# 612_jetracer_esp32s3_030003.net
KiCad netlist of a schematic drawn in EAGLE
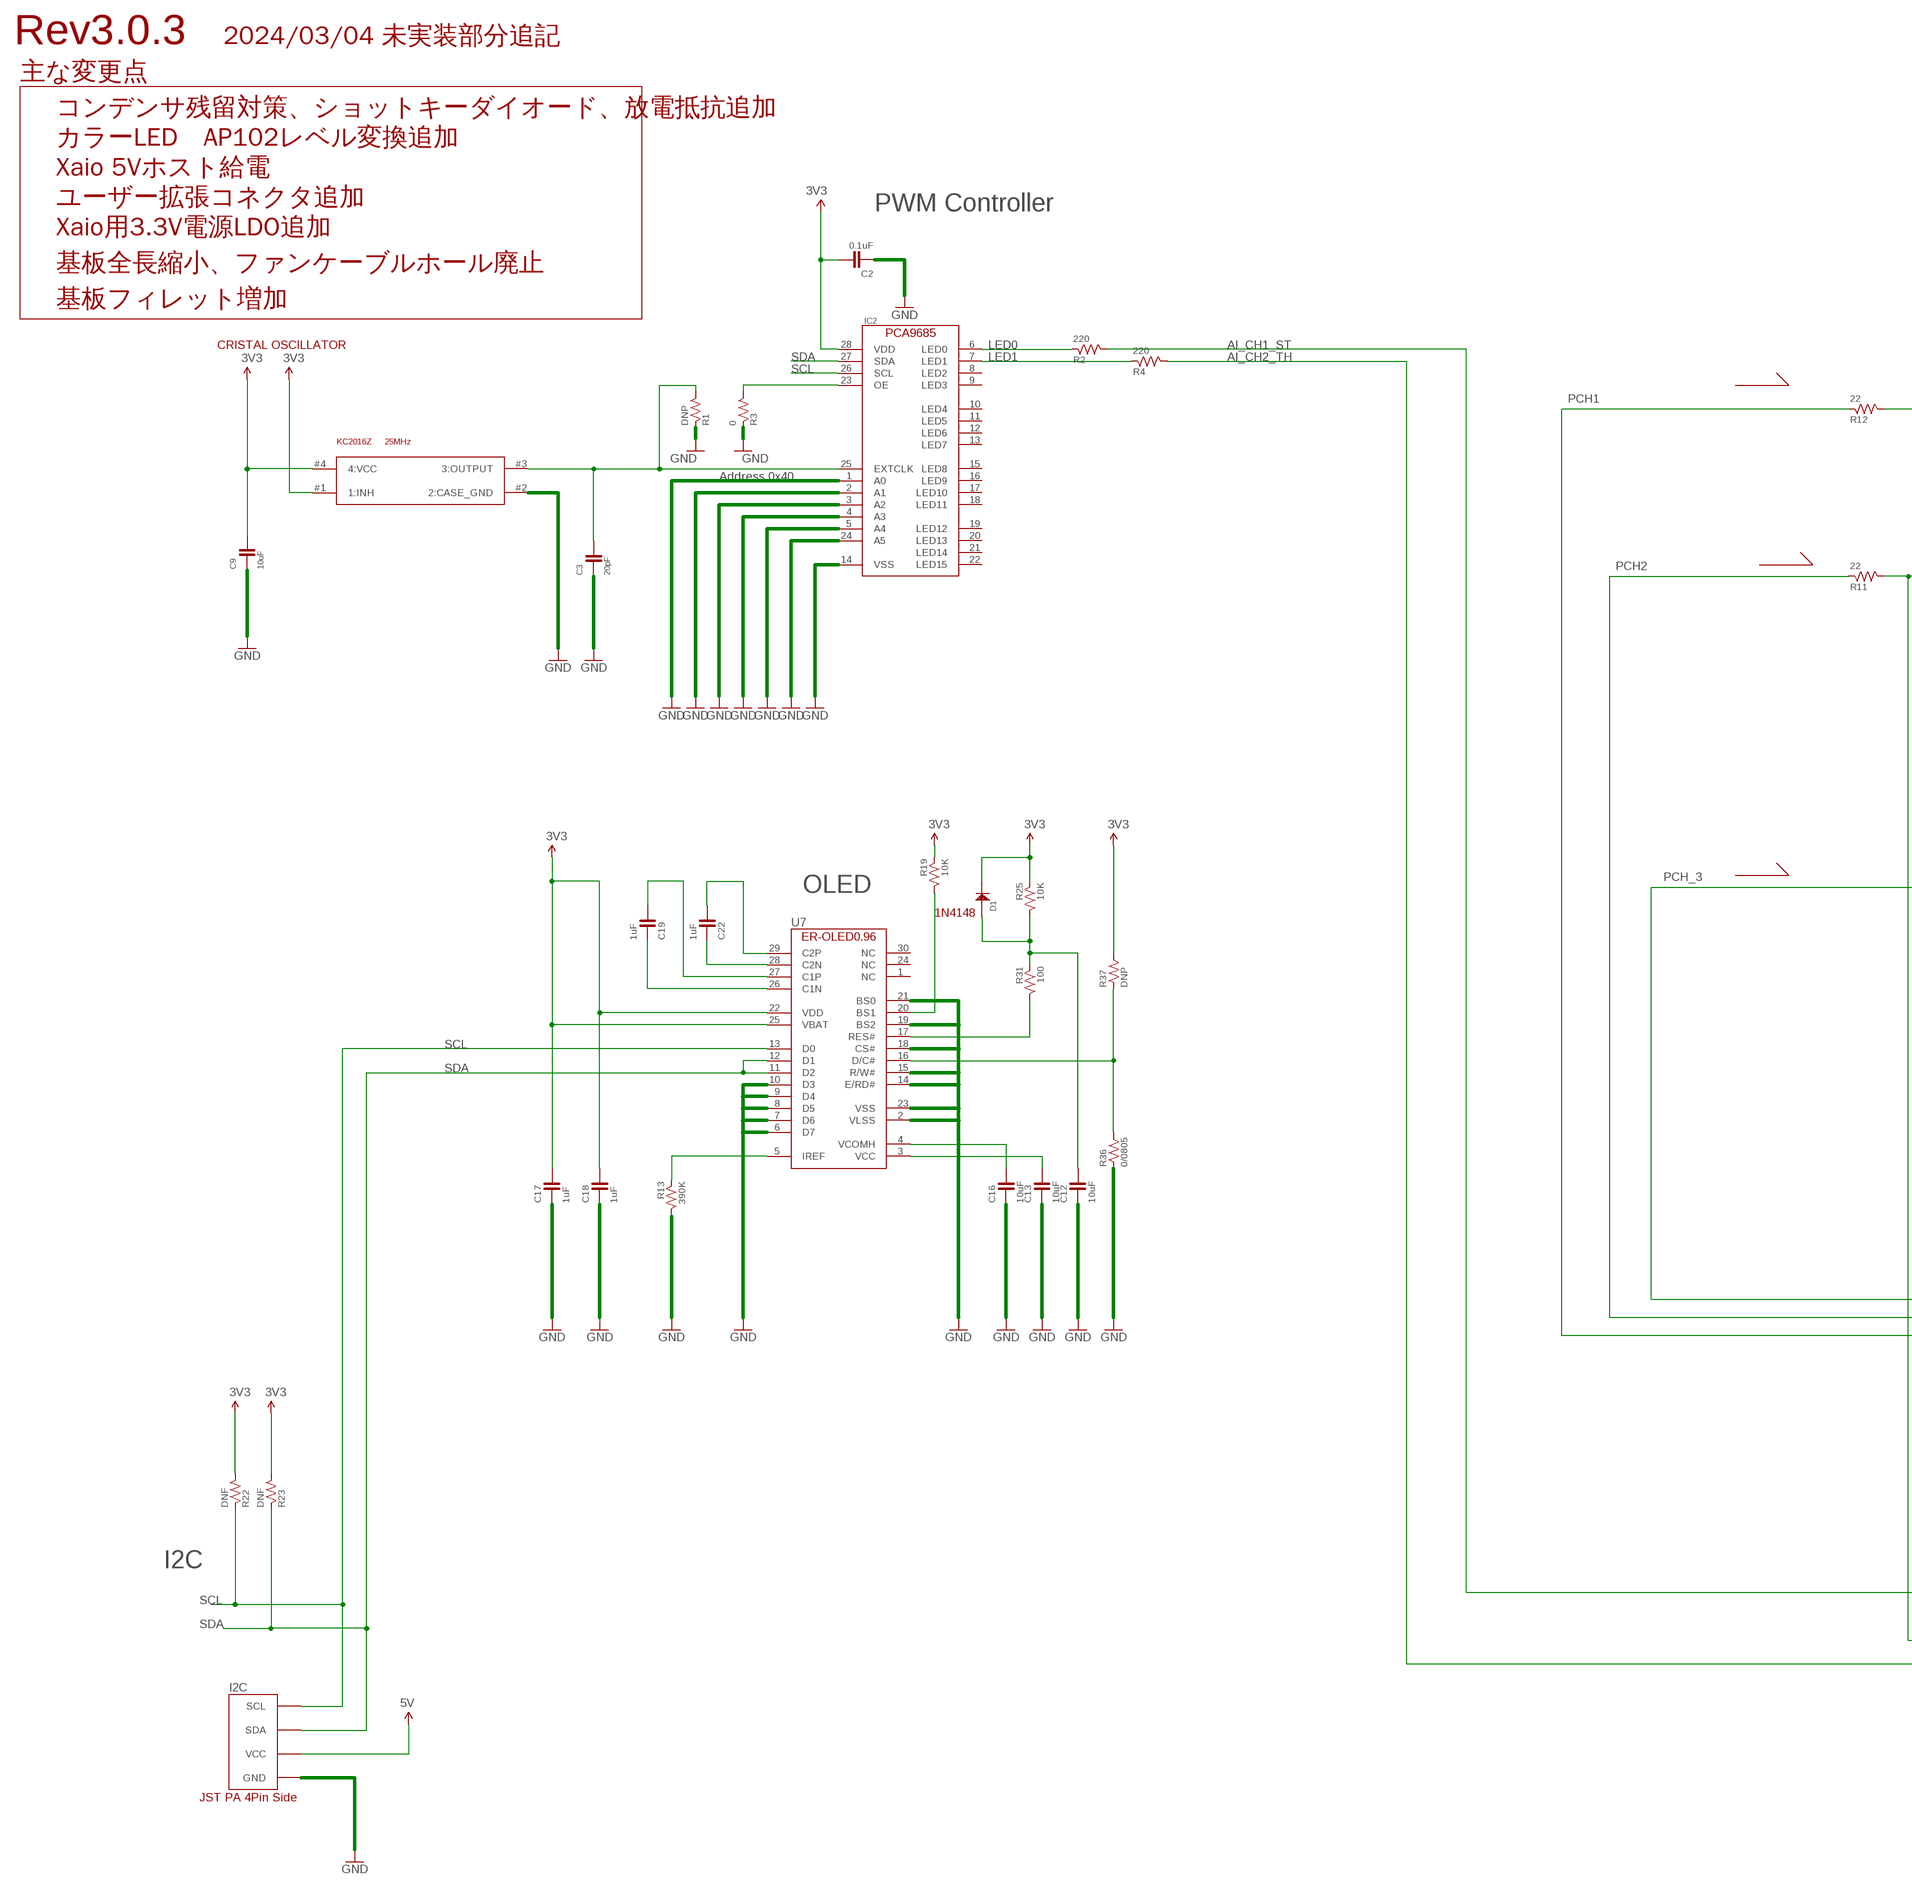
[diagram p0: schematic, sheet 1, part 1 of 3]
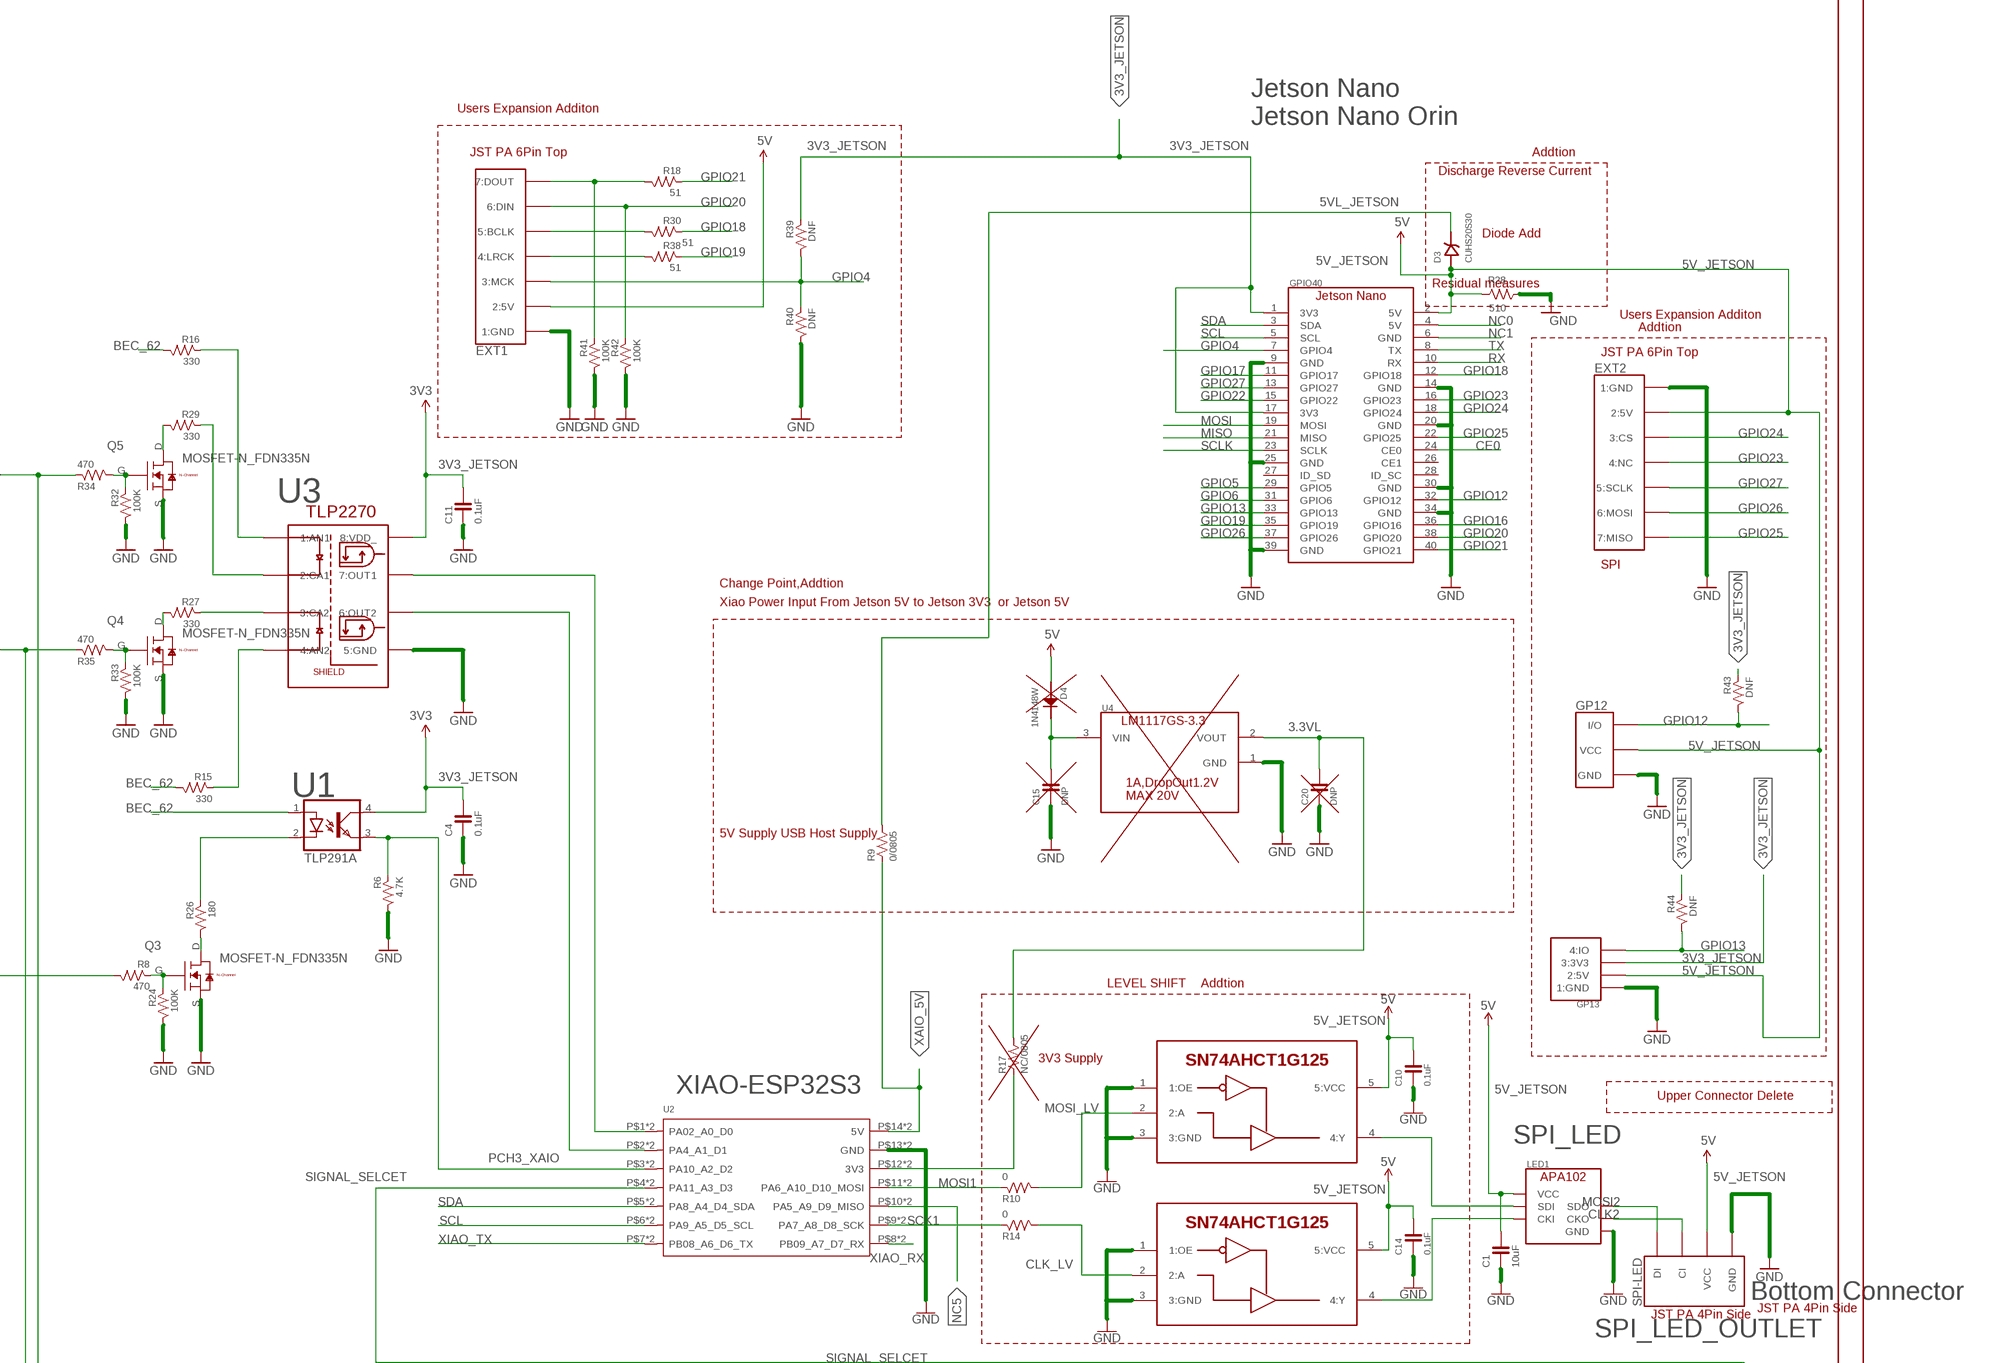
[diagram p1: schematic, sheet 1, part 2 of 3]
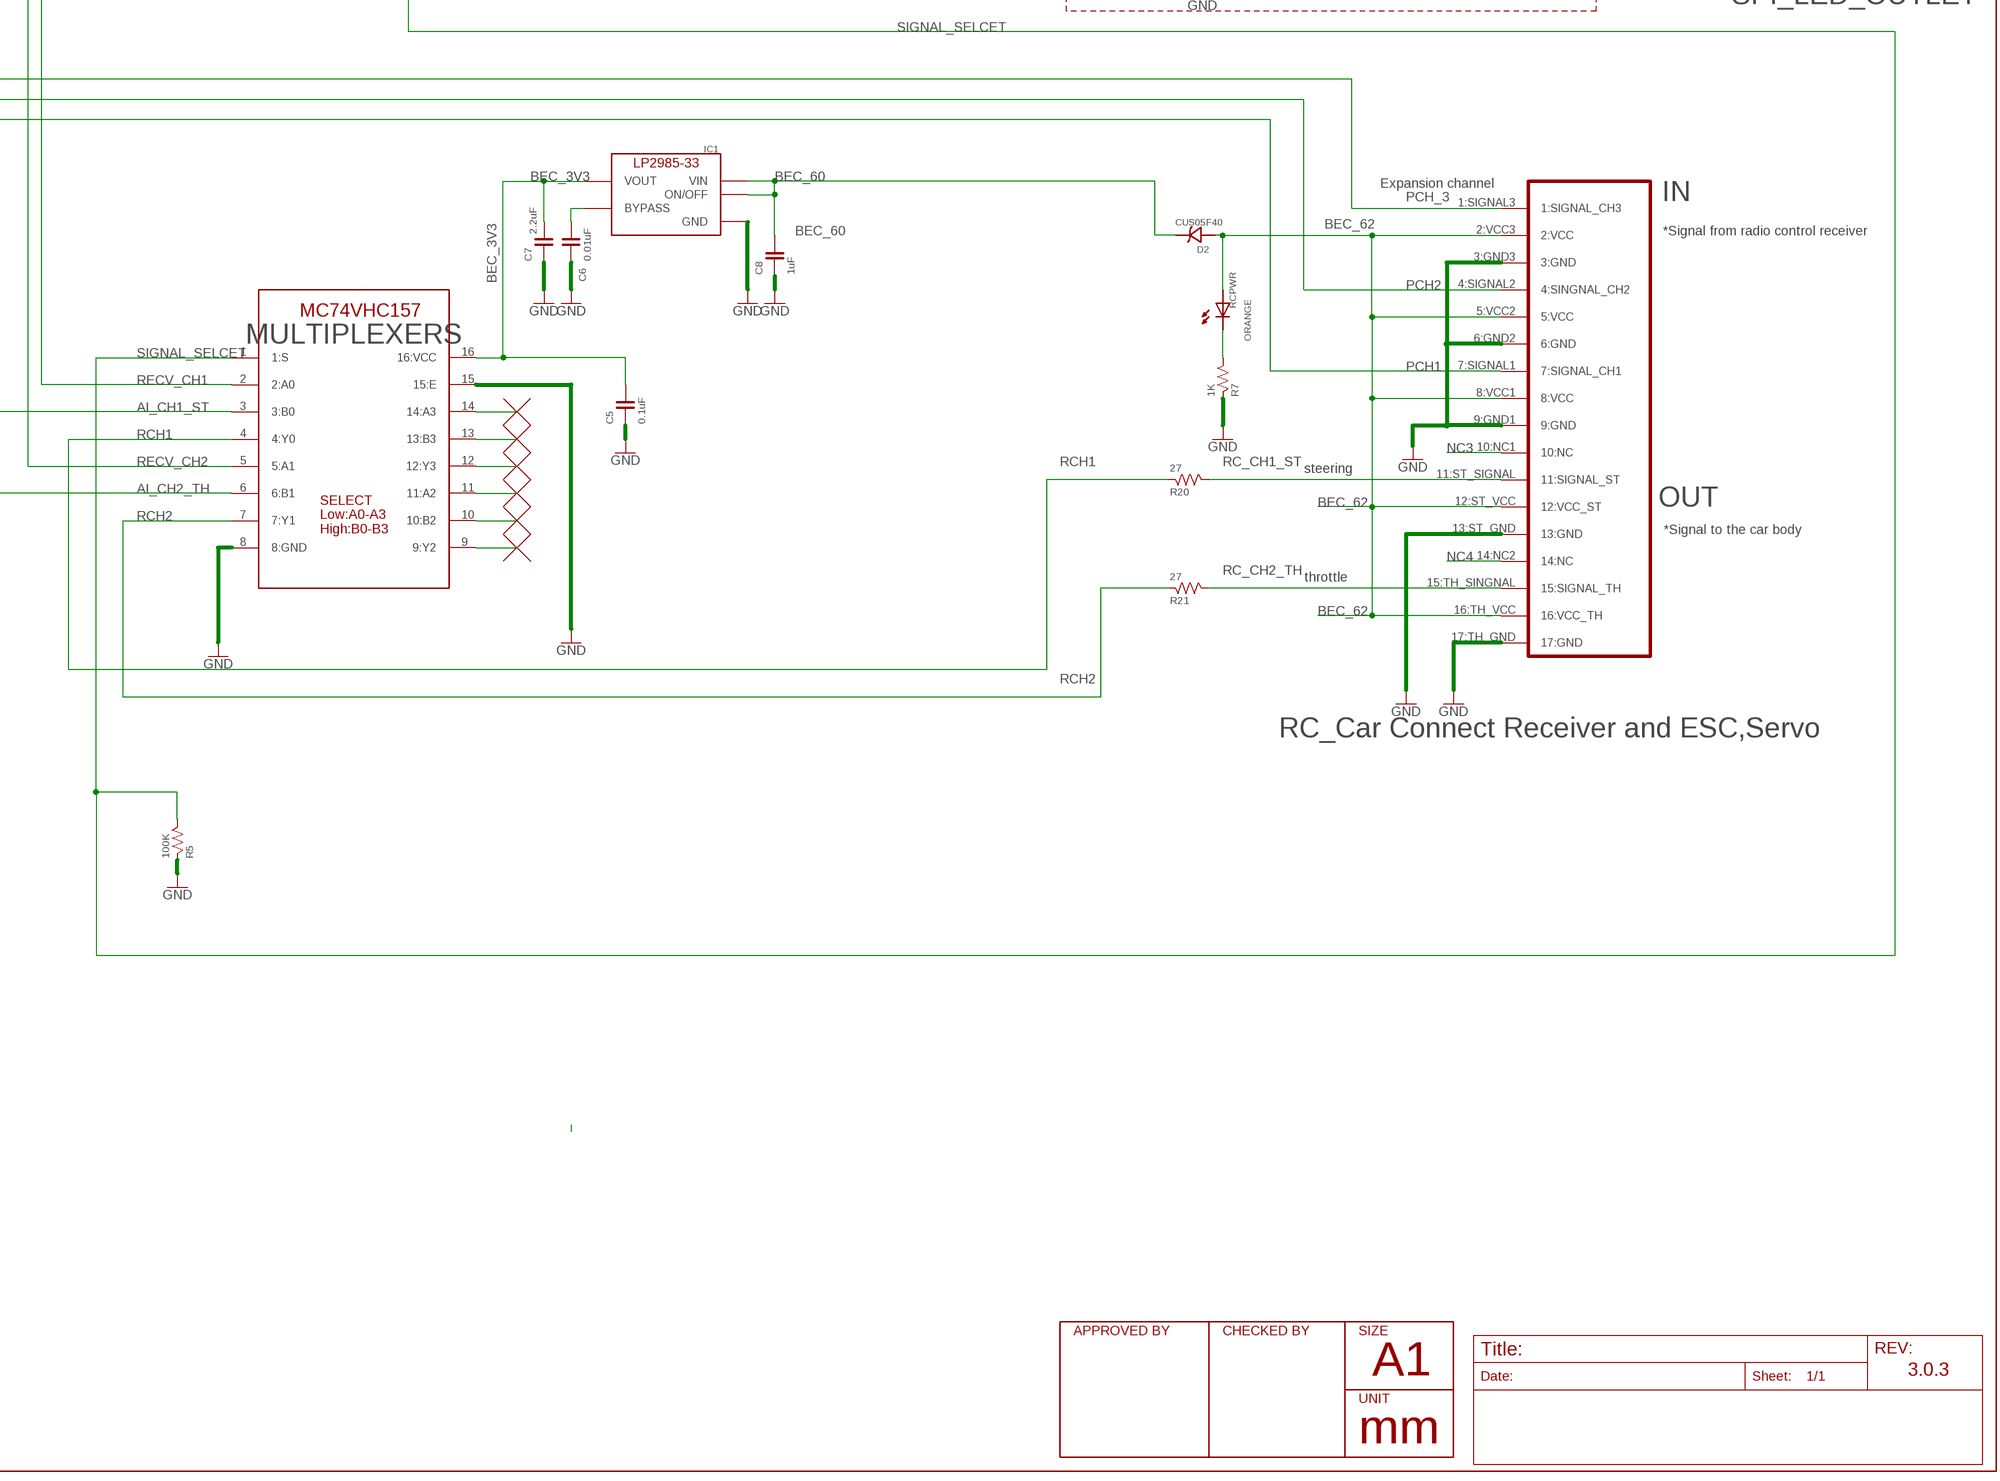
[diagram p2: schematic, sheet 1, part 3 of 3]

(export (version "E")
  (design (tool "Eeschema 10.0.6"))
  (components
    (comp (ref "C1")
      (value "10uF")
      (footprint "eagle-import:0603")
      (libsource (lib "eagle-import") (part "CAPACITOR-0603"))
    )
    (comp (ref "C2")
      (value "0.1uF")
      (footprint "eagle-import:0603")
      (libsource (lib "eagle-import") (part "CAPACITOR-0603"))
    )
    (comp (ref "C3")
      (value "20pF")
      (footprint "eagle-import:0402")
      (libsource (lib "eagle-import") (part "CAPACITOR-0402"))
    )
    (comp (ref "C4")
      (value "0.1uF")
      (footprint "eagle-import:0603")
      (libsource (lib "eagle-import") (part "CAPACITOR-0603"))
    )
    (comp (ref "C5")
      (value "0.1uF")
      (footprint "eagle-import:0603")
      (libsource (lib "eagle-import") (part "CAPACITOR-0603"))
    )
    (comp (ref "C6")
      (value "0.01uF")
      (footprint "eagle-import:0603")
      (libsource (lib "eagle-import") (part "CAPACITOR-0603"))
    )
    (comp (ref "C7")
      (value "2.2uF")
      (footprint "eagle-import:0603")
      (libsource (lib "eagle-import") (part "CAPACITOR-0603"))
    )
    (comp (ref "C8")
      (value "1uF")
      (footprint "eagle-import:0603")
      (libsource (lib "eagle-import") (part "CAPACITOR-0603"))
    )
    (comp (ref "C9")
      (value "10uF")
      (footprint "eagle-import:0402")
      (libsource (lib "eagle-import") (part "CAPACITOR-0402"))
    )
    (comp (ref "C10")
      (value "0.1uF")
      (footprint "eagle-import:0402")
      (libsource (lib "eagle-import") (part "CAPACITOR-0402"))
    )
    (comp (ref "C11")
      (value "0.1uF")
      (footprint "eagle-import:0603")
      (libsource (lib "eagle-import") (part "CAPACITOR-0603"))
    )
    (comp (ref "C12")
      (value "10uF")
      (footprint "eagle-import:0603")
      (libsource (lib "eagle-import") (part "CAPACITOR-0603"))
    )
    (comp (ref "C13")
      (value "10uF")
      (footprint "eagle-import:0603")
      (libsource (lib "eagle-import") (part "CAPACITOR-0603"))
    )
    (comp (ref "C14")
      (value "0.1uF")
      (footprint "eagle-import:0402")
      (libsource (lib "eagle-import") (part "CAPACITOR-0402"))
    )
    (comp (ref "C15")
      (value "DNP")
      (footprint "eagle-import:0402")
      (libsource (lib "eagle-import") (part "CAPACITOR-0402"))
    )
    (comp (ref "C16")
      (value "10uF")
      (footprint "eagle-import:0603")
      (libsource (lib "eagle-import") (part "CAPACITOR-0603"))
    )
    (comp (ref "C17")
      (value "1uF")
      (footprint "eagle-import:0603")
      (libsource (lib "eagle-import") (part "CAPACITOR-0603"))
    )
    (comp (ref "C18")
      (value "1uF")
      (footprint "eagle-import:0603")
      (libsource (lib "eagle-import") (part "CAPACITOR-0603"))
    )
    (comp (ref "C19")
      (value "1uF")
      (footprint "eagle-import:0603")
      (libsource (lib "eagle-import") (part "CAPACITOR-0603"))
    )
    (comp (ref "C20")
      (value "DNP")
      (footprint "eagle-import:0402")
      (libsource (lib "eagle-import") (part "CAPACITOR-0402"))
    )
    (comp (ref "C22")
      (value "1uF")
      (footprint "eagle-import:0603")
      (libsource (lib "eagle-import") (part "CAPACITOR-0603"))
    )
    (comp (ref "D1")
      (value "1N4148")
      (footprint "eagle-import:1N4148W")
      (libsource (lib "eagle-import") (part "1N4148"))
    )
    (comp (ref "D2")
      (value "CUS05F40")
      (footprint "eagle-import:CUS05F40")
      (libsource (lib "eagle-import") (part "CUS05F40"))
    )
    (comp (ref "D3")
      (value "CUHS20S30")
      (footprint "eagle-import:US2H")
      (libsource (lib "eagle-import") (part "CUHS20S30"))
    )
    (comp (ref "D4")
      (value "1N4148W")
      (footprint "eagle-import:SOD-123")
      (libsource (lib "eagle-import") (part "1N4148W"))
    )
    (comp (ref "EXT1")
      (value "FABO-I2S-7PIN")
      (footprint "eagle-import:SPI-B07B-PASK-1")
      (libsource (lib "eagle-import") (part "FABO-I2S-7PIN"))
    )
    (comp (ref "EXT2")
      (value "FABO-SPI-7PIN")
      (footprint "eagle-import:SPI-B07B-PASK-1")
      (libsource (lib "eagle-import") (part "FABO-SPI-7PIN"))
    )
    (comp (ref "GP12")
      (value "FABO_BRICK_3PIN-B03B-PASK-1")
      (footprint "eagle-import:FABO_BRICK_3PIN_B03B-PASK-1")
      (libsource (lib "eagle-import") (part "FABO_BRICK_3PIN-B03B-PASK-1"))
    )
    (comp (ref "GP13")
      (value "FABO-GPIO-2G")
      (footprint "eagle-import:GPIO-B04B-PASK-1")
      (libsource (lib "eagle-import") (part "FABO-GPIO-2G"))
    )
    (comp (ref "GPIO40")
      (value "JETSON_NANOJETSON_NANO_OVERALL")
      (footprint "eagle-import:JETSON_NANO_DEMENTION")
      (libsource (lib "eagle-import") (part "JETSON_NANOJETSON_NANO_OVERALL"))
    )
    (comp (ref "I2C")
      (value "FABO-I2C")
      (footprint "eagle-import:I2C-SM04B-PASS-1-FL")
      (libsource (lib "eagle-import") (part "FABO-I2C"))
    )
    (comp (ref "IC1")
      (value "LP2985-33DBVR")
      (footprint "eagle-import:SOT-23-5")
      (libsource (lib "eagle-import") (part "LP2985-33DBVR"))
    )
    (comp (ref "IC2")
      (value "PCA9685PW,BS")
      (footprint "eagle-import:PCA9685")
      (libsource (lib "eagle-import") (part "PCA9685PW,BS"))
    )
    (comp (ref "LED1")
      (value "APA102_IPIXEL")
      (footprint "eagle-import:APA102_2020")
      (libsource (lib "eagle-import") (part "APA102_IPIXEL"))
    )
    (comp (ref "Q3")
      (value "MOSFET-N_FDN335N")
      (footprint "eagle-import:SUPERSOT-3")
      (libsource (lib "eagle-import") (part "MOSFET-N_FDN335N"))
    )
    (comp (ref "Q4")
      (value "MOSFET-N_FDN335N")
      (footprint "eagle-import:SUPERSOT-3")
      (libsource (lib "eagle-import") (part "MOSFET-N_FDN335N"))
    )
    (comp (ref "Q5")
      (value "MOSFET-N_FDN335N")
      (footprint "eagle-import:SUPERSOT-3")
      (libsource (lib "eagle-import") (part "MOSFET-N_FDN335N"))
    )
    (comp (ref "R1")
      (value "DNP")
      (footprint "eagle-import:0603")
      (libsource (lib "eagle-import") (part "RESISTOR-0603"))
    )
    (comp (ref "R2")
      (value "220")
      (footprint "eagle-import:0603")
      (libsource (lib "eagle-import") (part "RESISTOR-0603"))
    )
    (comp (ref "R3")
      (value "0")
      (footprint "eagle-import:0603")
      (libsource (lib "eagle-import") (part "RESISTOR-0603"))
    )
    (comp (ref "R4")
      (value "220")
      (footprint "eagle-import:0603")
      (libsource (lib "eagle-import") (part "RESISTOR-0603"))
    )
    (comp (ref "R5")
      (value "100K")
      (footprint "eagle-import:0603")
      (libsource (lib "eagle-import") (part "RESISTOR-0603"))
    )
    (comp (ref "R6")
      (value "4.7K")
      (footprint "eagle-import:0603")
      (libsource (lib "eagle-import") (part "RESISTOR-0603"))
    )
    (comp (ref "R7")
      (value "1K")
      (footprint "eagle-import:0603")
      (libsource (lib "eagle-import") (part "RESISTOR-0603"))
    )
    (comp (ref "R8")
      (value "470")
      (footprint "eagle-import:0603")
      (libsource (lib "eagle-import") (part "RESISTOR-0603"))
    )
    (comp (ref "R9")
      (value "0/0805")
      (footprint "eagle-import:0805")
      (libsource (lib "eagle-import") (part "RESISTOR-0805"))
    )
    (comp (ref "R10")
      (value "0")
      (footprint "eagle-import:0603")
      (libsource (lib "eagle-import") (part "RESISTOR-0603"))
    )
    (comp (ref "R11")
      (value "22")
      (footprint "eagle-import:0603")
      (libsource (lib "eagle-import") (part "RESISTOR-0603"))
    )
    (comp (ref "R12")
      (value "22")
      (footprint "eagle-import:0603")
      (libsource (lib "eagle-import") (part "RESISTOR-0603"))
    )
    (comp (ref "R13")
      (value "390K")
      (footprint "eagle-import:0603")
      (libsource (lib "eagle-import") (part "RESISTOR-0603"))
    )
    (comp (ref "R14")
      (value "0")
      (footprint "eagle-import:0603")
      (libsource (lib "eagle-import") (part "RESISTOR-0603"))
    )
    (comp (ref "R15")
      (value "330")
      (footprint "eagle-import:0603")
      (libsource (lib "eagle-import") (part "RESISTOR-0603"))
    )
    (comp (ref "R16")
      (value "330")
      (footprint "eagle-import:0603")
      (libsource (lib "eagle-import") (part "RESISTOR-0603"))
    )
    (comp (ref "R17")
      (value "NC/0805")
      (footprint "eagle-import:0805")
      (libsource (lib "eagle-import") (part "RESISTOR-0805"))
    )
    (comp (ref "R18")
      (value "51")
      (footprint "eagle-import:0603")
      (libsource (lib "eagle-import") (part "RESISTOR-0603"))
    )
    (comp (ref "R19")
      (value "10K")
      (footprint "eagle-import:0603")
      (libsource (lib "eagle-import") (part "RESISTOR-0603"))
    )
    (comp (ref "R20")
      (value "27")
      (footprint "eagle-import:0603")
      (libsource (lib "eagle-import") (part "RESISTOR-0603"))
    )
    (comp (ref "R21")
      (value "27")
      (footprint "eagle-import:0603")
      (libsource (lib "eagle-import") (part "RESISTOR-0603"))
    )
    (comp (ref "R22")
      (value "DNF")
      (footprint "eagle-import:0603")
      (libsource (lib "eagle-import") (part "RESISTOR-0603"))
    )
    (comp (ref "R23")
      (value "DNF")
      (footprint "eagle-import:0603")
      (libsource (lib "eagle-import") (part "RESISTOR-0603"))
    )
    (comp (ref "R24")
      (value "100K")
      (footprint "eagle-import:0603")
      (libsource (lib "eagle-import") (part "RESISTOR-0603"))
    )
    (comp (ref "R25")
      (value "10K")
      (footprint "eagle-import:0603")
      (libsource (lib "eagle-import") (part "RESISTOR-0603"))
    )
    (comp (ref "R26")
      (value "180")
      (footprint "eagle-import:0603")
      (libsource (lib "eagle-import") (part "RESISTOR-0603"))
    )
    (comp (ref "R27")
      (value "330")
      (footprint "eagle-import:0603")
      (libsource (lib "eagle-import") (part "RESISTOR-0603"))
    )
    (comp (ref "R28")
      (value "510")
      (footprint "eagle-import:0805")
      (libsource (lib "eagle-import") (part "RESISTOR-0805"))
    )
    (comp (ref "R29")
      (value "330")
      (footprint "eagle-import:0603")
      (libsource (lib "eagle-import") (part "RESISTOR-0603"))
    )
    (comp (ref "R30")
      (value "51")
      (footprint "eagle-import:0603")
      (libsource (lib "eagle-import") (part "RESISTOR-0603"))
    )
    (comp (ref "R31")
      (value "100")
      (footprint "eagle-import:0603")
      (libsource (lib "eagle-import") (part "RESISTOR-0603"))
    )
    (comp (ref "R32")
      (value "100K")
      (footprint "eagle-import:0603")
      (libsource (lib "eagle-import") (part "RESISTOR-0603"))
    )
    (comp (ref "R33")
      (value "100K")
      (footprint "eagle-import:0603")
      (libsource (lib "eagle-import") (part "RESISTOR-0603"))
    )
    (comp (ref "R34")
      (value "470")
      (footprint "eagle-import:0603")
      (libsource (lib "eagle-import") (part "RESISTOR-0603"))
    )
    (comp (ref "R35")
      (value "470")
      (footprint "eagle-import:0603")
      (libsource (lib "eagle-import") (part "RESISTOR-0603"))
    )
    (comp (ref "R36")
      (value "0/0805")
      (footprint "eagle-import:0805")
      (libsource (lib "eagle-import") (part "RESISTOR-0805"))
    )
    (comp (ref "R37")
      (value "DNP")
      (footprint "eagle-import:0805")
      (fields (field (name "SPICEPREFIX") "R"))
      (libsource (lib "eagle-import") (part "RESISTOR-0805"))
    )
    (comp (ref "R38")
      (value "51")
      (footprint "eagle-import:0603")
      (libsource (lib "eagle-import") (part "RESISTOR-0603"))
    )
    (comp (ref "R39")
      (value "DNF")
      (footprint "eagle-import:0603")
      (libsource (lib "eagle-import") (part "RESISTOR-0603"))
    )
    (comp (ref "R40")
      (value "DNF")
      (footprint "eagle-import:0603")
      (libsource (lib "eagle-import") (part "RESISTOR-0603"))
    )
    (comp (ref "R41")
      (value "100K")
      (footprint "eagle-import:0603")
      (libsource (lib "eagle-import") (part "RESISTOR-0603"))
    )
    (comp (ref "R42")
      (value "100K")
      (footprint "eagle-import:0603")
      (libsource (lib "eagle-import") (part "RESISTOR-0603"))
    )
    (comp (ref "R43")
      (value "DNF")
      (footprint "eagle-import:0603")
      (libsource (lib "eagle-import") (part "RESISTOR-0603"))
    )
    (comp (ref "R44")
      (value "DNF")
      (footprint "eagle-import:0603")
      (libsource (lib "eagle-import") (part "RESISTOR-0603"))
    )
    (comp (ref "RCPWR")
      (value "ORANGE")
      (footprint "eagle-import:0603")
      (libsource (lib "eagle-import") (part "LED-0603"))
    )
    (comp (ref "SPI-LED")
      (value "FABO-SPI-LED")
      (footprint "eagle-import:SPI-SM04B-PASS-1-FL")
      (libsource (lib "eagle-import") (part "FABO-SPI-LED"))
    )
    (comp (ref "U$1")
      (value "RC_17PIN_OUTIN")
      (footprint "eagle-import:PNHEADER_2.54_SMT_17PIN_RC_TT01_02")
      (libsource (lib "eagle-import") (part "RC_17PIN_OUTIN"))
    )
    (comp (ref "U$3")
      (value "MC74VHC157")
      (footprint "eagle-import:MC74VHC157_TSSOP-16")
      (libsource (lib "eagle-import") (part "MC74VHC157"))
    )
    (comp (ref "U$9")
      (value "SN74AHCT1G125")
      (footprint "eagle-import:SOT-1DOT1")
      (libsource (lib "eagle-import") (part "SN74AHCT1G125"))
    )
    (comp (ref "U$10")
      (value "SN74AHCT1G125")
      (footprint "eagle-import:SOT-1DOT1")
      (libsource (lib "eagle-import") (part "SN74AHCT1G125"))
    )
    (comp (ref "U$11")
      (value "KC2016Z")
      (footprint "eagle-import:KC2016Z")
      (libsource (lib "eagle-import") (part "KC2016Z"))
    )
    (comp (ref "U1")
      (value "TLP291A")
      (footprint "eagle-import:11-3C1")
      (libsource (lib "eagle-import") (part "TLP291A"))
    )
    (comp (ref "U2")
      (value "MOUDLE-SEEEDUINO-XIAO-ESP32C3")
      (footprint "eagle-import:MOUDLE14P-DIP")
      (libsource (lib "eagle-import") (part "MOUDLE-SEEEDUINO-XIAO-ESP32C3"))
    )
    (comp (ref "U3")
      (value "TLP2270")
      (footprint "eagle-import:TLP2270")
      (libsource (lib "eagle-import") (part "TLP2270"))
    )
    (comp (ref "U4")
      (value "LM1117GS-3.3")
      (footprint "eagle-import:SOT-223-3")
      (libsource (lib "eagle-import") (part "LM1117GS-3.3"))
    )
    (comp (ref "U7")
      (value "ER-OLED0.96-1ER-CON30HT-1")
      (footprint "eagle-import:ER-CON30HT-1")
      (libsource (lib "eagle-import") (part "ER-OLED0.96-1ER-CON30HT-1"))
    )
  )
  (nets
    (net (code "1") (name "/3.3VL") (class "Default")
      (node (ref "C20") (pin "2") (pinfunction "2_2") (pintype "passive"))
      (node (ref "R17") (pin "2") (pinfunction "2_2") (pintype "bidirectional"))
      (node (ref "U4") (pin "2") (pinfunction "VOUT_2") (pintype "output"))
    )
    (net (code "2") (name "/5VL_JETSON") (class "Default")
      (node (ref "D3") (pin "K") (pinfunction "CATHODE_K") (pintype "passive"))
      (node (ref "R9") (pin "2") (pinfunction "2_2") (pintype "bidirectional"))
    )
    (net (code "3") (name "/AI_CH1_ST") (class "Default")
      (node (ref "R2") (pin "2") (pinfunction "2_2") (pintype "bidirectional"))
      (node (ref "U$3") (pin "3") (pinfunction "3:B0_3") (pintype "bidirectional"))
    )
    (net (code "4") (name "/AI_CH2_TH") (class "Default")
      (node (ref "R4") (pin "2") (pinfunction "2_2") (pintype "bidirectional"))
      (node (ref "U$3") (pin "6") (pinfunction "6:B1_6") (pintype "bidirectional"))
    )
    (net (code "5") (name "/BEC_3V3") (class "Default")
      (node (ref "C5") (pin "2") (pinfunction "2_2") (pintype "passive"))
      (node (ref "C7") (pin "2") (pinfunction "2_2") (pintype "passive"))
      (node (ref "IC1") (pin "5") (pinfunction "VOUT_5") (pintype "output"))
      (node (ref "U$3") (pin "16") (pinfunction "16:VCC_16") (pintype "bidirectional"))
    )
    (net (code "6") (name "/BEC_60") (class "Default")
      (node (ref "C8") (pin "2") (pinfunction "2_2") (pintype "passive"))
      (node (ref "D2") (pin "C") (pinfunction "CATHODE_C") (pintype "bidirectional"))
      (node (ref "IC1") (pin "1") (pinfunction "VIN_1") (pintype "input"))
      (node (ref "IC1") (pin "3") (pinfunction "ON/OFF_3") (pintype "input"))
    )
    (net (code "7") (name "/BEC_62") (class "Default")
      (node (ref "D2") (pin "A") (pinfunction "ANODE_A") (pintype "bidirectional"))
      (node (ref "R15") (pin "2") (pinfunction "2_2") (pintype "bidirectional"))
      (node (ref "R16") (pin "2") (pinfunction "2_2") (pintype "bidirectional"))
      (node (ref "RCPWR") (pin "ANODE") (pinfunction "ANODE_ANODE") (pintype "passive"))
      (node (ref "U$1") (pin "12:ST_VCC") (pinfunction "12:VCC_ST_12:ST_VCC") (pintype "bidirectional"))
      (node (ref "U$1") (pin "16:TH_VCC") (pinfunction "16:VCC_TH_16:TH_VCC") (pintype "bidirectional"))
      (node (ref "U$1") (pin "2:VCC3") (pinfunction "2:VCC_2:VCC3") (pintype "bidirectional"))
      (node (ref "U$1") (pin "5:VCC2") (pinfunction "5:VCC_5:VCC2") (pintype "bidirectional"))
      (node (ref "U$1") (pin "8:VCC1") (pinfunction "8:VCC_8:VCC1") (pintype "bidirectional"))
      (node (ref "U1") (pin "1") (pinfunction "A_1") (pintype "passive"))
    )
    (net (code "8") (name "/CE0") (class "Default")
      (node (ref "GPIO40") (pin "24") (pinfunction "CE0_24") (pintype "bidirectional"))
    )
    (net (code "9") (name "/CLK2") (class "Default")
      (node (ref "LED1") (pin "CKO") (pinfunction "CKO_CKO") (pintype "bidirectional"))
      (node (ref "SPI-LED") (pin "CI") (pinfunction "CI_CI") (pintype "bidirectional"))
    )
    (net (code "10") (name "/CLK_LV") (class "Default")
      (node (ref "R14") (pin "2") (pinfunction "2_2") (pintype "bidirectional"))
      (node (ref "U$10") (pin "2") (pinfunction "2:A_2") (pintype "input"))
    )
    (net (code "11") (name "/GPIO4") (class "Default")
      (node (ref "EXT1") (pin "3") (pinfunction "3:MCK_3") (pintype "bidirectional"))
      (node (ref "GPIO40") (pin "7") (pinfunction "GPIO4_7") (pintype "bidirectional"))
      (node (ref "R39") (pin "2") (pinfunction "2_2") (pintype "bidirectional"))
      (node (ref "R40") (pin "1") (pinfunction "1_1") (pintype "bidirectional"))
    )
    (net (code "12") (name "/GPIO5") (class "Default")
      (node (ref "GPIO40") (pin "29") (pinfunction "GPIO5_29") (pintype "bidirectional"))
    )
    (net (code "13") (name "/GPIO6") (class "Default")
      (node (ref "GPIO40") (pin "31") (pinfunction "GPIO6_31") (pintype "bidirectional"))
    )
    (net (code "14") (name "/GPIO12") (class "Default")
      (node (ref "GP12") (pin "I/O") (pinfunction "I/O_I/O") (pintype "bidirectional"))
      (node (ref "GPIO40") (pin "32") (pinfunction "GPIO12_32") (pintype "bidirectional"))
      (node (ref "R43") (pin "2") (pinfunction "2_2") (pintype "bidirectional"))
    )
    (net (code "15") (name "/GPIO13") (class "Default")
      (node (ref "GP13") (pin "IO") (pinfunction "4:IO_IO") (pintype "bidirectional"))
      (node (ref "GPIO40") (pin "33") (pinfunction "GPIO13_33") (pintype "bidirectional"))
      (node (ref "R44") (pin "2") (pinfunction "2_2") (pintype "bidirectional"))
    )
    (net (code "16") (name "/GPIO16") (class "Default")
      (node (ref "GPIO40") (pin "36") (pinfunction "GPIO16_36") (pintype "bidirectional"))
    )
    (net (code "17") (name "/GPIO17") (class "Default")
      (node (ref "GPIO40") (pin "11") (pinfunction "GPIO17_11") (pintype "bidirectional"))
    )
    (net (code "18") (name "/GPIO18") (class "Default")
      (node (ref "GPIO40") (pin "12") (pinfunction "GPIO18_12") (pintype "bidirectional"))
      (node (ref "R30") (pin "1") (pinfunction "1_1") (pintype "bidirectional"))
    )
    (net (code "19") (name "/GPIO19") (class "Default")
      (node (ref "GPIO40") (pin "35") (pinfunction "GPIO19_35") (pintype "bidirectional"))
      (node (ref "R38") (pin "1") (pinfunction "1_1") (pintype "bidirectional"))
    )
    (net (code "20") (name "/GPIO20") (class "Default")
      (node (ref "EXT1") (pin "6") (pinfunction "6:DIN_6") (pintype "bidirectional"))
      (node (ref "GPIO40") (pin "38") (pinfunction "GPIO20_38") (pintype "bidirectional"))
      (node (ref "R42") (pin "1") (pinfunction "1_1") (pintype "bidirectional"))
    )
    (net (code "21") (name "/GPIO21") (class "Default")
      (node (ref "GPIO40") (pin "40") (pinfunction "GPIO21_40") (pintype "bidirectional"))
      (node (ref "R18") (pin "1") (pinfunction "1_1") (pintype "bidirectional"))
    )
    (net (code "22") (name "/GPIO22") (class "Default")
      (node (ref "GPIO40") (pin "15") (pinfunction "GPIO22_15") (pintype "bidirectional"))
    )
    (net (code "23") (name "/GPIO23") (class "Default")
      (node (ref "EXT2") (pin "4") (pinfunction "4:NC_4") (pintype "bidirectional"))
      (node (ref "GPIO40") (pin "16") (pinfunction "GPIO23_16") (pintype "bidirectional"))
    )
    (net (code "24") (name "/GPIO24") (class "Default")
      (node (ref "EXT2") (pin "3") (pinfunction "3:CS_3") (pintype "bidirectional"))
      (node (ref "GPIO40") (pin "18") (pinfunction "GPIO24_18") (pintype "bidirectional"))
    )
    (net (code "25") (name "/GPIO25") (class "Default")
      (node (ref "EXT2") (pin "7") (pinfunction "7:MISO_7") (pintype "bidirectional"))
      (node (ref "GPIO40") (pin "22") (pinfunction "GPIO25_22") (pintype "bidirectional"))
    )
    (net (code "26") (name "/GPIO26") (class "Default")
      (node (ref "EXT2") (pin "6") (pinfunction "6:MOSI_6") (pintype "bidirectional"))
      (node (ref "GPIO40") (pin "37") (pinfunction "GPIO26_37") (pintype "bidirectional"))
    )
    (net (code "27") (name "/GPIO27") (class "Default")
      (node (ref "EXT2") (pin "5") (pinfunction "5:SCLK_5") (pintype "bidirectional"))
      (node (ref "GPIO40") (pin "13") (pinfunction "GPIO27_13") (pintype "bidirectional"))
    )
    (net (code "28") (name "/LED0") (class "Default")
      (node (ref "IC2") (pin "6") (pinfunction "LED0_6") (pintype "bidirectional"))
      (node (ref "R2") (pin "1") (pinfunction "1_1") (pintype "bidirectional"))
    )
    (net (code "29") (name "/LED1") (class "Default")
      (node (ref "IC2") (pin "7") (pinfunction "LED1_7") (pintype "bidirectional"))
      (node (ref "R4") (pin "1") (pinfunction "1_1") (pintype "bidirectional"))
    )
    (net (code "30") (name "/MISO") (class "Default")
      (node (ref "GPIO40") (pin "21") (pinfunction "MISO_21") (pintype "bidirectional"))
    )
    (net (code "31") (name "/MOSI") (class "Default")
      (node (ref "GPIO40") (pin "19") (pinfunction "MOSI_19") (pintype "bidirectional"))
    )
    (net (code "32") (name "/MOSI1") (class "Default")
      (node (ref "R10") (pin "1") (pinfunction "1_1") (pintype "bidirectional"))
      (node (ref "U2") (pin "P$11") (pinfunction "PA6_A10_D10_MOSI_P$11") (pintype "bidirectional"))
      (node (ref "U2") (pin "P$25") (pinfunction "PA6_A10_D10_MOSI_P$25") (pintype "bidirectional"))
    )
    (net (code "33") (name "/MOSI2") (class "Default")
      (node (ref "LED1") (pin "SDO") (pinfunction "SDO_SDO") (pintype "bidirectional"))
      (node (ref "SPI-LED") (pin "DI") (pinfunction "DI_DI") (pintype "bidirectional"))
    )
    (net (code "34") (name "/MOSI_LV") (class "Default")
      (node (ref "R10") (pin "2") (pinfunction "2_2") (pintype "bidirectional"))
      (node (ref "U$9") (pin "2") (pinfunction "2:A_2") (pintype "input"))
    )
    (net (code "35") (name "/NC0") (class "Default")
      (node (ref "GPIO40") (pin "4") (pinfunction "5V_4") (pintype "bidirectional"))
    )
    (net (code "36") (name "/NC1") (class "Default")
      (node (ref "GPIO40") (pin "6") (pinfunction "GND_6") (pintype "bidirectional"))
    )
    (net (code "37") (name "/NC3") (class "Default")
      (node (ref "U$1") (pin "10:NC1") (pinfunction "10:NC_10:NC1") (pintype "bidirectional"))
    )
    (net (code "38") (name "/NC4") (class "Default")
      (node (ref "U$1") (pin "14:NC2") (pinfunction "14:NC_14:NC2") (pintype "bidirectional"))
    )
    (net (code "39") (name "/PCH1") (class "Default")
      (node (ref "R12") (pin "1") (pinfunction "1_1") (pintype "bidirectional"))
      (node (ref "U$1") (pin "7:SIGNAL1") (pinfunction "7:SIGNAL_CH1_7:SIGNAL1") (pintype "bidirectional"))
    )
    (net (code "40") (name "/PCH2") (class "Default")
      (node (ref "R11") (pin "1") (pinfunction "1_1") (pintype "bidirectional"))
      (node (ref "U$1") (pin "4:SIGNAL2") (pinfunction "4:SINGNAL_CH2_4:SIGNAL2") (pintype "bidirectional"))
    )
    (net (code "41") (name "/PCH3_XAIO") (class "Default")
      (node (ref "R6") (pin "1") (pinfunction "1_1") (pintype "bidirectional"))
      (node (ref "U1") (pin "3") (pinfunction "EMI_3") (pintype "passive"))
      (node (ref "U2") (pin "P$17") (pinfunction "PA10_A2_D2_P$17") (pintype "bidirectional"))
      (node (ref "U2") (pin "P$3") (pinfunction "PA10_A2_D2_P$3") (pintype "bidirectional"))
    )
    (net (code "42") (name "/PCH_3") (class "Default")
      (node (ref "R8") (pin "2") (pinfunction "2_2") (pintype "bidirectional"))
      (node (ref "U$1") (pin "1:SIGNAL3") (pinfunction "1:SIGNAL_CH3_1:SIGNAL3") (pintype "bidirectional"))
    )
    (net (code "43") (name "/RCH1") (class "Default")
      (node (ref "R20") (pin "1") (pinfunction "1_1") (pintype "bidirectional"))
      (node (ref "U$3") (pin "4") (pinfunction "4:Y0_4") (pintype "bidirectional"))
    )
    (net (code "44") (name "/RCH2") (class "Default")
      (node (ref "R21") (pin "1") (pinfunction "1_1") (pintype "bidirectional"))
      (node (ref "U$3") (pin "7") (pinfunction "7:Y1_7") (pintype "bidirectional"))
    )
    (net (code "45") (name "/RC_CH1_ST") (class "Default")
      (node (ref "R20") (pin "2") (pinfunction "2_2") (pintype "bidirectional"))
      (node (ref "U$1") (pin "11:ST_SIGNAL") (pinfunction "11:SIGNAL_ST_11:ST_SIGNAL") (pintype "bidirectional"))
    )
    (net (code "46") (name "/RC_CH2_TH") (class "Default")
      (node (ref "R21") (pin "2") (pinfunction "2_2") (pintype "bidirectional"))
      (node (ref "U$1") (pin "15:TH_SINGNAL") (pinfunction "15:SIGNAL_TH_15:TH_SINGNAL") (pintype "bidirectional"))
    )
    (net (code "47") (name "/RECV_CH1") (class "Default")
      (node (ref "R12") (pin "2") (pinfunction "2_2") (pintype "bidirectional"))
      (node (ref "R34") (pin "1") (pinfunction "1_1") (pintype "bidirectional"))
      (node (ref "U$3") (pin "2") (pinfunction "2:A0_2") (pintype "bidirectional"))
    )
    (net (code "48") (name "/RECV_CH2") (class "Default")
      (node (ref "R11") (pin "2") (pinfunction "2_2") (pintype "bidirectional"))
      (node (ref "R35") (pin "1") (pinfunction "1_1") (pintype "bidirectional"))
      (node (ref "U$3") (pin "5") (pinfunction "5:A1_5") (pintype "bidirectional"))
    )
    (net (code "49") (name "/RX") (class "Default")
      (node (ref "GPIO40") (pin "10") (pinfunction "RX_10") (pintype "bidirectional"))
    )
    (net (code "50") (name "/SCK1") (class "Default")
      (node (ref "R14") (pin "1") (pinfunction "1_1") (pintype "bidirectional"))
      (node (ref "U2") (pin "P$23") (pinfunction "PA7_A8_D8_SCK_P$23") (pintype "bidirectional"))
      (node (ref "U2") (pin "P$9") (pinfunction "PA7_A8_D8_SCK_P$9") (pintype "bidirectional"))
    )
    (net (code "51") (name "/SCL") (class "Default")
      (node (ref "GPIO40") (pin "5") (pinfunction "SCL_5") (pintype "bidirectional"))
      (node (ref "I2C") (pin "SCL") (pinfunction "SCL_SCL") (pintype "bidirectional"))
      (node (ref "IC2") (pin "26") (pinfunction "SCL_26") (pintype "bidirectional"))
      (node (ref "R22") (pin "1") (pinfunction "1_1") (pintype "bidirectional"))
      (node (ref "U2") (pin "P$20") (pinfunction "PA9_A5_D5_SCL_P$20") (pintype "bidirectional"))
      (node (ref "U2") (pin "P$6") (pinfunction "PA9_A5_D5_SCL_P$6") (pintype "bidirectional"))
      (node (ref "U7") (pin "13") (pinfunction "D0_13") (pintype "bidirectional"))
    )
    (net (code "52") (name "/SCLK") (class "Default")
      (node (ref "GPIO40") (pin "23") (pinfunction "SCLK_23") (pintype "bidirectional"))
    )
    (net (code "53") (name "/SDA") (class "Default")
      (node (ref "GPIO40") (pin "3") (pinfunction "SDA_3") (pintype "bidirectional"))
      (node (ref "I2C") (pin "SDA") (pinfunction "SDA_SDA") (pintype "bidirectional"))
      (node (ref "IC2") (pin "27") (pinfunction "SDA_27") (pintype "bidirectional"))
      (node (ref "R23") (pin "1") (pinfunction "1_1") (pintype "bidirectional"))
      (node (ref "U2") (pin "P$19") (pinfunction "PA8_A4_D4_SDA_P$19") (pintype "bidirectional"))
      (node (ref "U2") (pin "P$5") (pinfunction "PA8_A4_D4_SDA_P$5") (pintype "bidirectional"))
      (node (ref "U7") (pin "11") (pinfunction "D2_11") (pintype "bidirectional"))
      (node (ref "U7") (pin "12") (pinfunction "D1_12") (pintype "bidirectional"))
    )
    (net (code "54") (name "/SIGNAL_SELCET") (class "Default")
      (node (ref "R5") (pin "2") (pinfunction "2_2") (pintype "bidirectional"))
      (node (ref "U$3") (pin "1") (pinfunction "1:S_1") (pintype "bidirectional"))
      (node (ref "U2") (pin "P$18") (pinfunction "PA11_A3_D3_P$18") (pintype "bidirectional"))
      (node (ref "U2") (pin "P$4") (pinfunction "PA11_A3_D3_P$4") (pintype "bidirectional"))
    )
    (net (code "55") (name "/TX") (class "Default")
      (node (ref "GPIO40") (pin "8") (pinfunction "TX_8") (pintype "bidirectional"))
    )
    (net (code "56") (name "/XIAO_RX") (class "Default")
      (node (ref "U2") (pin "P$22") (pinfunction "PB09_A7_D7_RX_P$22") (pintype "bidirectional"))
      (node (ref "U2") (pin "P$8") (pinfunction "PB09_A7_D7_RX_P$8") (pintype "bidirectional"))
    )
    (net (code "57") (name "/XIAO_TX") (class "Default")
      (node (ref "U2") (pin "P$21") (pinfunction "PB08_A6_D6_TX_P$21") (pintype "bidirectional"))
      (node (ref "U2") (pin "P$7") (pinfunction "PB08_A6_D6_TX_P$7") (pintype "bidirectional"))
    )
    (net (code "58") (name "3V3_JETSON") (class "Default")
      (node (ref "C11") (pin "2") (pinfunction "2_2") (pintype "passive"))
      (node (ref "C17") (pin "2") (pinfunction "2_2") (pintype "passive"))
      (node (ref "C18") (pin "2") (pinfunction "2_2") (pintype "passive"))
      (node (ref "C2") (pin "2") (pinfunction "2_2") (pintype "passive"))
      (node (ref "C4") (pin "2") (pinfunction "2_2") (pintype "passive"))
      (node (ref "C9") (pin "2") (pinfunction "2_2") (pintype "passive"))
      (node (ref "D1") (pin "CATHODE") (pinfunction "CATHODE_CATHODE") (pintype "bidirectional"))
      (node (ref "GP13") (pin "3V3") (pinfunction "3:3V3_3V3") (pintype "bidirectional"))
      (node (ref "GPIO40") (pin "1") (pinfunction "3V3_1") (pintype "bidirectional"))
      (node (ref "GPIO40") (pin "17") (pinfunction "3V3_17") (pintype "bidirectional"))
      (node (ref "IC2") (pin "28") (pinfunction "VDD_28") (pintype "bidirectional"))
      (node (ref "R19") (pin "1") (pinfunction "1_1") (pintype "bidirectional"))
      (node (ref "R22") (pin "2") (pinfunction "2_2") (pintype "bidirectional"))
      (node (ref "R23") (pin "2") (pinfunction "2_2") (pintype "bidirectional"))
      (node (ref "R25") (pin "1") (pinfunction "1_1") (pintype "bidirectional"))
      (node (ref "R37") (pin "2") (pinfunction "2_2") (pintype "bidirectional"))
      (node (ref "R39") (pin "1") (pinfunction "1_1") (pintype "bidirectional"))
      (node (ref "R43") (pin "1") (pinfunction "1_1") (pintype "bidirectional"))
      (node (ref "R44") (pin "1") (pinfunction "1_1") (pintype "bidirectional"))
      (node (ref "U$11") (pin "#1") (pinfunction "1:INH_#1") (pintype "bidirectional"))
      (node (ref "U$11") (pin "#4") (pinfunction "4:VCC_#4") (pintype "bidirectional"))
      (node (ref "U1") (pin "4") (pinfunction "COL_4") (pintype "passive"))
      (node (ref "U3") (pin "8") (pinfunction "8:VDD__8") (pintype "bidirectional"))
      (node (ref "U7") (pin "22") (pinfunction "VDD_22") (pintype "bidirectional"))
      (node (ref "U7") (pin "25") (pinfunction "VBAT_25") (pintype "bidirectional"))
    )
    (net (code "59") (name "5V") (class "Default")
      (node (ref "C1") (pin "2") (pinfunction "2_2") (pintype "passive"))
      (node (ref "C10") (pin "2") (pinfunction "2_2") (pintype "passive"))
      (node (ref "C14") (pin "2") (pinfunction "2_2") (pintype "passive"))
      (node (ref "D3") (pin "A") (pinfunction "ANODE_A") (pintype "passive"))
      (node (ref "D4") (pin "2") (pinfunction "ANODE_2") (pintype "bidirectional"))
      (node (ref "EXT1") (pin "2") (pinfunction "2:5V_2") (pintype "bidirectional"))
      (node (ref "EXT2") (pin "2") (pinfunction "2:5V_2") (pintype "bidirectional"))
      (node (ref "GP12") (pin "VCC") (pinfunction "VCC_VCC") (pintype "bidirectional"))
      (node (ref "GP13") (pin "5V") (pinfunction "2:5V_5V") (pintype "bidirectional"))
      (node (ref "GPIO40") (pin "2") (pinfunction "5V_2") (pintype "bidirectional"))
      (node (ref "I2C") (pin "5V") (pinfunction "VCC_5V") (pintype "bidirectional"))
      (node (ref "LED1") (pin "VCC") (pinfunction "VCC_VCC") (pintype "bidirectional"))
      (node (ref "R28") (pin "2") (pinfunction "2_2") (pintype "bidirectional"))
      (node (ref "SPI-LED") (pin "5V") (pinfunction "VCC_5V") (pintype "bidirectional"))
      (node (ref "U$10") (pin "5") (pinfunction "5:VCC_5") (pintype "power_in"))
      (node (ref "U$9") (pin "5") (pinfunction "5:VCC_5") (pintype "power_in"))
    )
    (net (code "60") (name "GND") (class "Default")
      (node (ref "C1") (pin "1") (pinfunction "1_1") (pintype "passive"))
      (node (ref "C10") (pin "1") (pinfunction "1_1") (pintype "passive"))
      (node (ref "C11") (pin "1") (pinfunction "1_1") (pintype "passive"))
      (node (ref "C12") (pin "1") (pinfunction "1_1") (pintype "passive"))
      (node (ref "C13") (pin "1") (pinfunction "1_1") (pintype "passive"))
      (node (ref "C14") (pin "1") (pinfunction "1_1") (pintype "passive"))
      (node (ref "C15") (pin "1") (pinfunction "1_1") (pintype "passive"))
      (node (ref "C16") (pin "1") (pinfunction "1_1") (pintype "passive"))
      (node (ref "C17") (pin "1") (pinfunction "1_1") (pintype "passive"))
      (node (ref "C18") (pin "1") (pinfunction "1_1") (pintype "passive"))
      (node (ref "C2") (pin "1") (pinfunction "1_1") (pintype "passive"))
      (node (ref "C20") (pin "1") (pinfunction "1_1") (pintype "passive"))
      (node (ref "C3") (pin "1") (pinfunction "1_1") (pintype "passive"))
      (node (ref "C4") (pin "1") (pinfunction "1_1") (pintype "passive"))
      (node (ref "C5") (pin "1") (pinfunction "1_1") (pintype "passive"))
      (node (ref "C6") (pin "1") (pinfunction "1_1") (pintype "passive"))
      (node (ref "C7") (pin "1") (pinfunction "1_1") (pintype "passive"))
      (node (ref "C8") (pin "1") (pinfunction "1_1") (pintype "passive"))
      (node (ref "C9") (pin "1") (pinfunction "1_1") (pintype "passive"))
      (node (ref "EXT1") (pin "1") (pinfunction "1:GND_1") (pintype "bidirectional"))
      (node (ref "EXT2") (pin "1") (pinfunction "1:GND_1") (pintype "bidirectional"))
      (node (ref "GP12") (pin "GND") (pinfunction "GND_GND") (pintype "bidirectional"))
      (node (ref "GP13") (pin "GND") (pinfunction "1:GND_GND") (pintype "bidirectional"))
      (node (ref "GPIO40") (pin "14") (pinfunction "GND_14") (pintype "bidirectional"))
      (node (ref "GPIO40") (pin "20") (pinfunction "GND_20") (pintype "bidirectional"))
      (node (ref "GPIO40") (pin "25") (pinfunction "GND_25") (pintype "bidirectional"))
      (node (ref "GPIO40") (pin "30") (pinfunction "GND_30") (pintype "bidirectional"))
      (node (ref "GPIO40") (pin "34") (pinfunction "GND_34") (pintype "bidirectional"))
      (node (ref "GPIO40") (pin "39") (pinfunction "GND_39") (pintype "bidirectional"))
      (node (ref "GPIO40") (pin "9") (pinfunction "GND_9") (pintype "bidirectional"))
      (node (ref "I2C") (pin "GND") (pinfunction "GND_GND") (pintype "bidirectional"))
      (node (ref "IC1") (pin "2") (pinfunction "GND_2") (pintype "power_in"))
      (node (ref "IC2") (pin "1") (pinfunction "A0_1") (pintype "bidirectional"))
      (node (ref "IC2") (pin "14") (pinfunction "VSS_14") (pintype "bidirectional"))
      (node (ref "IC2") (pin "2") (pinfunction "A1_2") (pintype "bidirectional"))
      (node (ref "IC2") (pin "24") (pinfunction "A5_24") (pintype "bidirectional"))
      (node (ref "IC2") (pin "3") (pinfunction "A2_3") (pintype "bidirectional"))
      (node (ref "IC2") (pin "4") (pinfunction "A3_4") (pintype "bidirectional"))
      (node (ref "IC2") (pin "5") (pinfunction "A4_5") (pintype "bidirectional"))
      (node (ref "LED1") (pin "GND") (pinfunction "GND_GND") (pintype "bidirectional"))
      (node (ref "Q3") (pin "S") (pinfunction "S_S") (pintype "passive"))
      (node (ref "Q4") (pin "S") (pinfunction "S_S") (pintype "passive"))
      (node (ref "Q5") (pin "S") (pinfunction "S_S") (pintype "passive"))
      (node (ref "R1") (pin "1") (pinfunction "1_1") (pintype "bidirectional"))
      (node (ref "R13") (pin "2") (pinfunction "2_2") (pintype "bidirectional"))
      (node (ref "R24") (pin "2") (pinfunction "2_2") (pintype "bidirectional"))
      (node (ref "R28") (pin "1") (pinfunction "1_1") (pintype "bidirectional"))
      (node (ref "R3") (pin "1") (pinfunction "1_1") (pintype "bidirectional"))
      (node (ref "R32") (pin "2") (pinfunction "2_2") (pintype "bidirectional"))
      (node (ref "R33") (pin "2") (pinfunction "2_2") (pintype "bidirectional"))
      (node (ref "R36") (pin "1") (pinfunction "1_1") (pintype "bidirectional"))
      (node (ref "R40") (pin "2") (pinfunction "2_2") (pintype "bidirectional"))
      (node (ref "R41") (pin "2") (pinfunction "2_2") (pintype "bidirectional"))
      (node (ref "R42") (pin "2") (pinfunction "2_2") (pintype "bidirectional"))
      (node (ref "R5") (pin "1") (pinfunction "1_1") (pintype "bidirectional"))
      (node (ref "R6") (pin "2") (pinfunction "2_2") (pintype "bidirectional"))
      (node (ref "R7") (pin "1") (pinfunction "1_1") (pintype "bidirectional"))
      (node (ref "SPI-LED") (pin "GND") (pinfunction "GND_GND") (pintype "bidirectional"))
      (node (ref "U$1") (pin "13:ST_GND") (pinfunction "13:GND_13:ST_GND") (pintype "bidirectional"))
      (node (ref "U$1") (pin "17:TH_GND") (pinfunction "17:GND_17:TH_GND") (pintype "bidirectional"))
      (node (ref "U$1") (pin "3:GND3") (pinfunction "3:GND_3:GND3") (pintype "bidirectional"))
      (node (ref "U$1") (pin "6:GND2") (pinfunction "6:GND_6:GND2") (pintype "bidirectional"))
      (node (ref "U$1") (pin "9:GND1") (pinfunction "9:GND_9:GND1") (pintype "bidirectional"))
      (node (ref "U$10") (pin "1") (pinfunction "1:OE_1") (pintype "input"))
      (node (ref "U$10") (pin "3") (pinfunction "3:GND_3") (pintype "power_in"))
      (node (ref "U$11") (pin "#2") (pinfunction "2:CASE_GND_#2") (pintype "bidirectional"))
      (node (ref "U$3") (pin "15") (pinfunction "15:E_15") (pintype "bidirectional"))
      (node (ref "U$3") (pin "8") (pinfunction "8:GND_8") (pintype "bidirectional"))
      (node (ref "U$9") (pin "1") (pinfunction "1:OE_1") (pintype "input"))
      (node (ref "U$9") (pin "3") (pinfunction "3:GND_3") (pintype "power_in"))
      (node (ref "U2") (pin "P$13") (pinfunction "GND_P$13") (pintype "bidirectional"))
      (node (ref "U2") (pin "P$27") (pinfunction "GND_P$27") (pintype "bidirectional"))
      (node (ref "U3") (pin "5") (pinfunction "5:GND_5") (pintype "bidirectional"))
      (node (ref "U4") (pin "1") (pinfunction "GND_1") (pintype "power_in"))
      (node (ref "U7") (pin "10") (pinfunction "D3_10") (pintype "bidirectional"))
      (node (ref "U7") (pin "14") (pinfunction "E/RD#_14") (pintype "bidirectional"))
      (node (ref "U7") (pin "15") (pinfunction "R/W#_15") (pintype "bidirectional"))
      (node (ref "U7") (pin "18") (pinfunction "CS#_18") (pintype "bidirectional"))
      (node (ref "U7") (pin "19") (pinfunction "BS2_19") (pintype "bidirectional"))
      (node (ref "U7") (pin "2") (pinfunction "VLSS_2") (pintype "bidirectional"))
      (node (ref "U7") (pin "21") (pinfunction "BS0_21") (pintype "bidirectional"))
      (node (ref "U7") (pin "23") (pinfunction "VSS_23") (pintype "bidirectional"))
      (node (ref "U7") (pin "6") (pinfunction "D7_6") (pintype "bidirectional"))
      (node (ref "U7") (pin "7") (pinfunction "D6_7") (pintype "bidirectional"))
      (node (ref "U7") (pin "8") (pinfunction "D5_8") (pintype "bidirectional"))
      (node (ref "U7") (pin "9") (pinfunction "D4_9") (pintype "bidirectional"))
    )
    (net (code "61") (name "NC5") (class "Default")
      (node (ref "U2") (pin "P$10") (pinfunction "PA5_A9_D9_MISO_P$10") (pintype "bidirectional"))
      (node (ref "U2") (pin "P$24") (pinfunction "PA5_A9_D9_MISO_P$24") (pintype "bidirectional"))
    )
    (net (code "62") (name "Net-(C12-Pad2)") (class "Default")
      (node (ref "C12") (pin "2") (pinfunction "2_2") (pintype "passive"))
      (node (ref "D1") (pin "ANODE") (pinfunction "ANODE_ANODE") (pintype "bidirectional"))
      (node (ref "R25") (pin "2") (pinfunction "2_2") (pintype "bidirectional"))
      (node (ref "R31") (pin "1") (pinfunction "1_1") (pintype "bidirectional"))
    )
    (net (code "63") (name "Net-(D4-CATHODE)") (class "Default")
      (node (ref "C15") (pin "2") (pinfunction "2_2") (pintype "passive"))
      (node (ref "D4") (pin "1") (pinfunction "CATHODE_1") (pintype "bidirectional"))
      (node (ref "U4") (pin "3") (pinfunction "VIN_3") (pintype "input"))
    )
    (net (code "64") (name "Net-(EXT1-4:LRCK)") (class "Default")
      (node (ref "EXT1") (pin "4") (pinfunction "4:LRCK_4") (pintype "bidirectional"))
      (node (ref "R38") (pin "2") (pinfunction "2_2") (pintype "bidirectional"))
    )
    (net (code "65") (name "Net-(EXT1-5:BCLK)") (class "Default")
      (node (ref "EXT1") (pin "5") (pinfunction "5:BCLK_5") (pintype "bidirectional"))
      (node (ref "R30") (pin "2") (pinfunction "2_2") (pintype "bidirectional"))
    )
    (net (code "66") (name "Net-(EXT1-7:DOUT)") (class "Default")
      (node (ref "EXT1") (pin "7") (pinfunction "7:DOUT_7") (pintype "bidirectional"))
      (node (ref "R18") (pin "2") (pinfunction "2_2") (pintype "bidirectional"))
      (node (ref "R41") (pin "1") (pinfunction "1_1") (pintype "bidirectional"))
    )
    (net (code "67") (name "Net-(IC1-BYPASS)") (class "Default")
      (node (ref "C6") (pin "2") (pinfunction "2_2") (pintype "passive"))
      (node (ref "IC1") (pin "4") (pinfunction "BYPASS_4") (pintype "bidirectional"))
    )
    (net (code "68") (name "Net-(IC2-EXTCLK)") (class "Default")
      (node (ref "C3") (pin "2") (pinfunction "2_2") (pintype "passive"))
      (node (ref "IC2") (pin "25") (pinfunction "EXTCLK_25") (pintype "bidirectional"))
      (node (ref "R1") (pin "2") (pinfunction "2_2") (pintype "bidirectional"))
      (node (ref "U$11") (pin "#3") (pinfunction "3:OUTPUT_#3") (pintype "bidirectional"))
    )
    (net (code "69") (name "Net-(IC2-OE)") (class "Default")
      (node (ref "IC2") (pin "23") (pinfunction "OE_23") (pintype "bidirectional"))
      (node (ref "R3") (pin "2") (pinfunction "2_2") (pintype "bidirectional"))
    )
    (net (code "70") (name "Net-(Q3-PadD)") (class "Default")
      (node (ref "Q3") (pin "D") (pinfunction "D_D") (pintype "passive"))
      (node (ref "R26") (pin "2") (pinfunction "2_2") (pintype "bidirectional"))
    )
    (net (code "71") (name "Net-(Q3-PadG)") (class "Default")
      (node (ref "Q3") (pin "G") (pinfunction "G_G") (pintype "passive"))
      (node (ref "R24") (pin "1") (pinfunction "1_1") (pintype "bidirectional"))
      (node (ref "R8") (pin "1") (pinfunction "1_1") (pintype "bidirectional"))
    )
    (net (code "72") (name "Net-(Q4-PadD)") (class "Default")
      (node (ref "Q4") (pin "D") (pinfunction "D_D") (pintype "passive"))
      (node (ref "R27") (pin "2") (pinfunction "2_2") (pintype "bidirectional"))
    )
    (net (code "73") (name "Net-(Q4-PadG)") (class "Default")
      (node (ref "Q4") (pin "G") (pinfunction "G_G") (pintype "passive"))
      (node (ref "R33") (pin "1") (pinfunction "1_1") (pintype "bidirectional"))
      (node (ref "R35") (pin "2") (pinfunction "2_2") (pintype "bidirectional"))
    )
    (net (code "74") (name "Net-(Q5-PadD)") (class "Default")
      (node (ref "Q5") (pin "D") (pinfunction "D_D") (pintype "passive"))
      (node (ref "R29") (pin "2") (pinfunction "2_2") (pintype "bidirectional"))
    )
    (net (code "75") (name "Net-(Q5-PadG)") (class "Default")
      (node (ref "Q5") (pin "G") (pinfunction "G_G") (pintype "passive"))
      (node (ref "R32") (pin "1") (pinfunction "1_1") (pintype "bidirectional"))
      (node (ref "R34") (pin "2") (pinfunction "2_2") (pintype "bidirectional"))
    )
    (net (code "76") (name "Net-(R7-Pad2)") (class "Default")
      (node (ref "R7") (pin "2") (pinfunction "2_2") (pintype "bidirectional"))
      (node (ref "RCPWR") (pin "CATHODE") (pinfunction "CATHODE_CATHODE") (pintype "passive"))
    )
    (net (code "77") (name "Net-(R17-Pad1)") (class "Default")
      (node (ref "R17") (pin "1") (pinfunction "1_1") (pintype "bidirectional"))
      (node (ref "U2") (pin "P$12") (pinfunction "3V3_P$12") (pintype "bidirectional"))
      (node (ref "U2") (pin "P$26") (pinfunction "3V3_P$26") (pintype "bidirectional"))
    )
    (net (code "78") (name "Net-(U$9-4:Y)") (class "Default")
      (node (ref "LED1") (pin "SDI") (pinfunction "SDI_SDI") (pintype "bidirectional"))
      (node (ref "U$9") (pin "4") (pinfunction "4:Y_4") (pintype "output"))
    )
    (net (code "79") (name "Net-(U$10-4:Y)") (class "Default")
      (node (ref "LED1") (pin "CKI") (pinfunction "CKI_CKI") (pintype "bidirectional"))
      (node (ref "U$10") (pin "4") (pinfunction "4:Y_4") (pintype "output"))
    )
    (net (code "80") (name "Net-(U1-C)") (class "Default")
      (node (ref "R26") (pin "1") (pinfunction "1_1") (pintype "bidirectional"))
      (node (ref "U1") (pin "2") (pinfunction "C_2") (pintype "passive"))
    )
    (net (code "81") (name "Net-(U3-1:AN1)") (class "Default")
      (node (ref "R16") (pin "1") (pinfunction "1_1") (pintype "bidirectional"))
      (node (ref "U3") (pin "1") (pinfunction "1:AN1_1") (pintype "bidirectional"))
    )
    (net (code "82") (name "Net-(U3-2:CA1)") (class "Default")
      (node (ref "R29") (pin "1") (pinfunction "1_1") (pintype "bidirectional"))
      (node (ref "U3") (pin "2") (pinfunction "2:CA1_2") (pintype "bidirectional"))
    )
    (net (code "83") (name "Net-(U3-3:CA2)") (class "Default")
      (node (ref "R27") (pin "1") (pinfunction "1_1") (pintype "bidirectional"))
      (node (ref "U3") (pin "3") (pinfunction "3:CA2_3") (pintype "bidirectional"))
    )
    (net (code "84") (name "Net-(U3-4:AN2)") (class "Default")
      (node (ref "R15") (pin "1") (pinfunction "1_1") (pintype "bidirectional"))
      (node (ref "U3") (pin "4") (pinfunction "4:AN2_4") (pintype "bidirectional"))
    )
    (net (code "85") (name "Net-(U3-6:OUT2)") (class "Default")
      (node (ref "U2") (pin "P$16") (pinfunction "PA4_A1_D1_P$16") (pintype "bidirectional"))
      (node (ref "U2") (pin "P$2") (pinfunction "PA4_A1_D1_P$2") (pintype "bidirectional"))
      (node (ref "U3") (pin "6") (pinfunction "6:OUT2_6") (pintype "bidirectional"))
    )
    (net (code "86") (name "Net-(U3-7:OUT1)") (class "Default")
      (node (ref "U2") (pin "P$1") (pinfunction "PA02_A0_D0_P$1") (pintype "bidirectional"))
      (node (ref "U2") (pin "P$15") (pinfunction "PA02_A0_D0_P$15") (pintype "bidirectional"))
      (node (ref "U3") (pin "7") (pinfunction "7:OUT1_7") (pintype "bidirectional"))
    )
    (net (code "87") (name "Net-(U7-BS1)") (class "Default")
      (node (ref "R19") (pin "2") (pinfunction "2_2") (pintype "bidirectional"))
      (node (ref "U7") (pin "20") (pinfunction "BS1_20") (pintype "bidirectional"))
    )
    (net (code "88") (name "Net-(U7-C1N)") (class "Default")
      (node (ref "C19") (pin "1") (pinfunction "1_1") (pintype "passive"))
      (node (ref "U7") (pin "26") (pinfunction "C1N_26") (pintype "bidirectional"))
    )
    (net (code "89") (name "Net-(U7-C1P)") (class "Default")
      (node (ref "C19") (pin "2") (pinfunction "2_2") (pintype "passive"))
      (node (ref "U7") (pin "27") (pinfunction "C1P_27") (pintype "bidirectional"))
    )
    (net (code "90") (name "Net-(U7-C2N)") (class "Default")
      (node (ref "C22") (pin "1") (pinfunction "1_1") (pintype "passive"))
      (node (ref "U7") (pin "28") (pinfunction "C2N_28") (pintype "bidirectional"))
    )
    (net (code "91") (name "Net-(U7-C2P)") (class "Default")
      (node (ref "C22") (pin "2") (pinfunction "2_2") (pintype "passive"))
      (node (ref "U7") (pin "29") (pinfunction "C2P_29") (pintype "bidirectional"))
    )
    (net (code "92") (name "Net-(U7-D{slash}C#)") (class "Default")
      (node (ref "R36") (pin "2") (pinfunction "2_2") (pintype "bidirectional"))
      (node (ref "R37") (pin "1") (pinfunction "1_1") (pintype "bidirectional"))
      (node (ref "U7") (pin "16") (pinfunction "D/C#_16") (pintype "bidirectional"))
    )
    (net (code "93") (name "Net-(U7-IREF)") (class "Default")
      (node (ref "R13") (pin "1") (pinfunction "1_1") (pintype "bidirectional"))
      (node (ref "U7") (pin "5") (pinfunction "IREF_5") (pintype "bidirectional"))
    )
    (net (code "94") (name "Net-(U7-RES#)") (class "Default")
      (node (ref "R31") (pin "2") (pinfunction "2_2") (pintype "bidirectional"))
      (node (ref "U7") (pin "17") (pinfunction "RES#_17") (pintype "bidirectional"))
    )
    (net (code "95") (name "Net-(U7-VCC)") (class "Default")
      (node (ref "C13") (pin "2") (pinfunction "2_2") (pintype "passive"))
      (node (ref "U7") (pin "3") (pinfunction "VCC_3") (pintype "bidirectional"))
    )
    (net (code "96") (name "Net-(U7-VCOMH)") (class "Default")
      (node (ref "C16") (pin "2") (pinfunction "2_2") (pintype "passive"))
      (node (ref "U7") (pin "4") (pinfunction "VCOMH_4") (pintype "bidirectional"))
    )
    (net (code "97") (name "XAIO_5V") (class "Default")
      (node (ref "R9") (pin "1") (pinfunction "1_1") (pintype "bidirectional"))
      (node (ref "U2") (pin "P$14") (pinfunction "5V_P$14") (pintype "bidirectional"))
      (node (ref "U2") (pin "P$28") (pinfunction "5V_P$28") (pintype "bidirectional"))
    )
    (net (code "98") (name "unconnected-(GPIO40-CE1-Pad26)") (class "Default")
      (node (ref "GPIO40") (pin "26") (pinfunction "CE1_26") (pintype "bidirectional"))
    )
    (net (code "99") (name "unconnected-(GPIO40-ID_SC-Pad28)") (class "Default")
      (node (ref "GPIO40") (pin "28") (pinfunction "ID_SC_28") (pintype "bidirectional"))
    )
    (net (code "100") (name "unconnected-(GPIO40-ID_SD-Pad27)") (class "Default")
      (node (ref "GPIO40") (pin "27") (pinfunction "ID_SD_27") (pintype "bidirectional"))
    )
    (net (code "101") (name "unconnected-(IC2-LED2-Pad8)") (class "Default")
      (node (ref "IC2") (pin "8") (pinfunction "LED2_8") (pintype "bidirectional"))
    )
    (net (code "102") (name "unconnected-(IC2-LED3-Pad9)") (class "Default")
      (node (ref "IC2") (pin "9") (pinfunction "LED3_9") (pintype "bidirectional"))
    )
    (net (code "103") (name "unconnected-(IC2-LED4-Pad10)") (class "Default")
      (node (ref "IC2") (pin "10") (pinfunction "LED4_10") (pintype "bidirectional"))
    )
    (net (code "104") (name "unconnected-(IC2-LED5-Pad11)") (class "Default")
      (node (ref "IC2") (pin "11") (pinfunction "LED5_11") (pintype "bidirectional"))
    )
    (net (code "105") (name "unconnected-(IC2-LED6-Pad12)") (class "Default")
      (node (ref "IC2") (pin "12") (pinfunction "LED6_12") (pintype "bidirectional"))
    )
    (net (code "106") (name "unconnected-(IC2-LED7-Pad13)") (class "Default")
      (node (ref "IC2") (pin "13") (pinfunction "LED7_13") (pintype "bidirectional"))
    )
    (net (code "107") (name "unconnected-(IC2-LED8-Pad15)") (class "Default")
      (node (ref "IC2") (pin "15") (pinfunction "LED8_15") (pintype "bidirectional"))
    )
    (net (code "108") (name "unconnected-(IC2-LED9-Pad16)") (class "Default")
      (node (ref "IC2") (pin "16") (pinfunction "LED9_16") (pintype "bidirectional"))
    )
    (net (code "109") (name "unconnected-(IC2-LED10-Pad17)") (class "Default")
      (node (ref "IC2") (pin "17") (pinfunction "LED10_17") (pintype "bidirectional"))
    )
    (net (code "110") (name "unconnected-(IC2-LED11-Pad18)") (class "Default")
      (node (ref "IC2") (pin "18") (pinfunction "LED11_18") (pintype "bidirectional"))
    )
    (net (code "111") (name "unconnected-(IC2-LED12-Pad19)") (class "Default")
      (node (ref "IC2") (pin "19") (pinfunction "LED12_19") (pintype "bidirectional"))
    )
    (net (code "112") (name "unconnected-(IC2-LED13-Pad20)") (class "Default")
      (node (ref "IC2") (pin "20") (pinfunction "LED13_20") (pintype "bidirectional"))
    )
    (net (code "113") (name "unconnected-(IC2-LED14-Pad21)") (class "Default")
      (node (ref "IC2") (pin "21") (pinfunction "LED14_21") (pintype "bidirectional"))
    )
    (net (code "114") (name "unconnected-(IC2-LED15-Pad22)") (class "Default")
      (node (ref "IC2") (pin "22") (pinfunction "LED15_22") (pintype "bidirectional"))
    )
    (net (code "115") (name "unconnected-(U$3-9:Y2-Pad9)") (class "Default")
      (node (ref "U$3") (pin "9") (pinfunction "9:Y2_9") (pintype "bidirectional"))
    )
    (net (code "116") (name "unconnected-(U$3-10:B2-Pad10)") (class "Default")
      (node (ref "U$3") (pin "10") (pinfunction "10:B2_10") (pintype "bidirectional"))
    )
    (net (code "117") (name "unconnected-(U$3-11:A2-Pad11)") (class "Default")
      (node (ref "U$3") (pin "11") (pinfunction "11:A2_11") (pintype "bidirectional"))
    )
    (net (code "118") (name "unconnected-(U$3-12:Y3-Pad12)") (class "Default")
      (node (ref "U$3") (pin "12") (pinfunction "12:Y3_12") (pintype "bidirectional"))
    )
    (net (code "119") (name "unconnected-(U$3-13:B3-Pad13)") (class "Default")
      (node (ref "U$3") (pin "13") (pinfunction "13:B3_13") (pintype "bidirectional"))
    )
    (net (code "120") (name "unconnected-(U$3-14:A3-Pad14)") (class "Default")
      (node (ref "U$3") (pin "14") (pinfunction "14:A3_14") (pintype "bidirectional"))
    )
    (net (code "121") (name "unconnected-(U7-NC-Pad1)") (class "Default")
      (node (ref "U7") (pin "1") (pinfunction "NC_1") (pintype "bidirectional"))
    )
    (net (code "122") (name "unconnected-(U7-NC-Pad24)") (class "Default")
      (node (ref "U7") (pin "24") (pinfunction "NC_24") (pintype "bidirectional"))
    )
    (net (code "123") (name "unconnected-(U7-NC-Pad30)") (class "Default")
      (node (ref "U7") (pin "30") (pinfunction "NC_30") (pintype "bidirectional"))
    )
  )
)
